# owl-analog.net
KiCad netlist of a schematic drawn in EAGLE
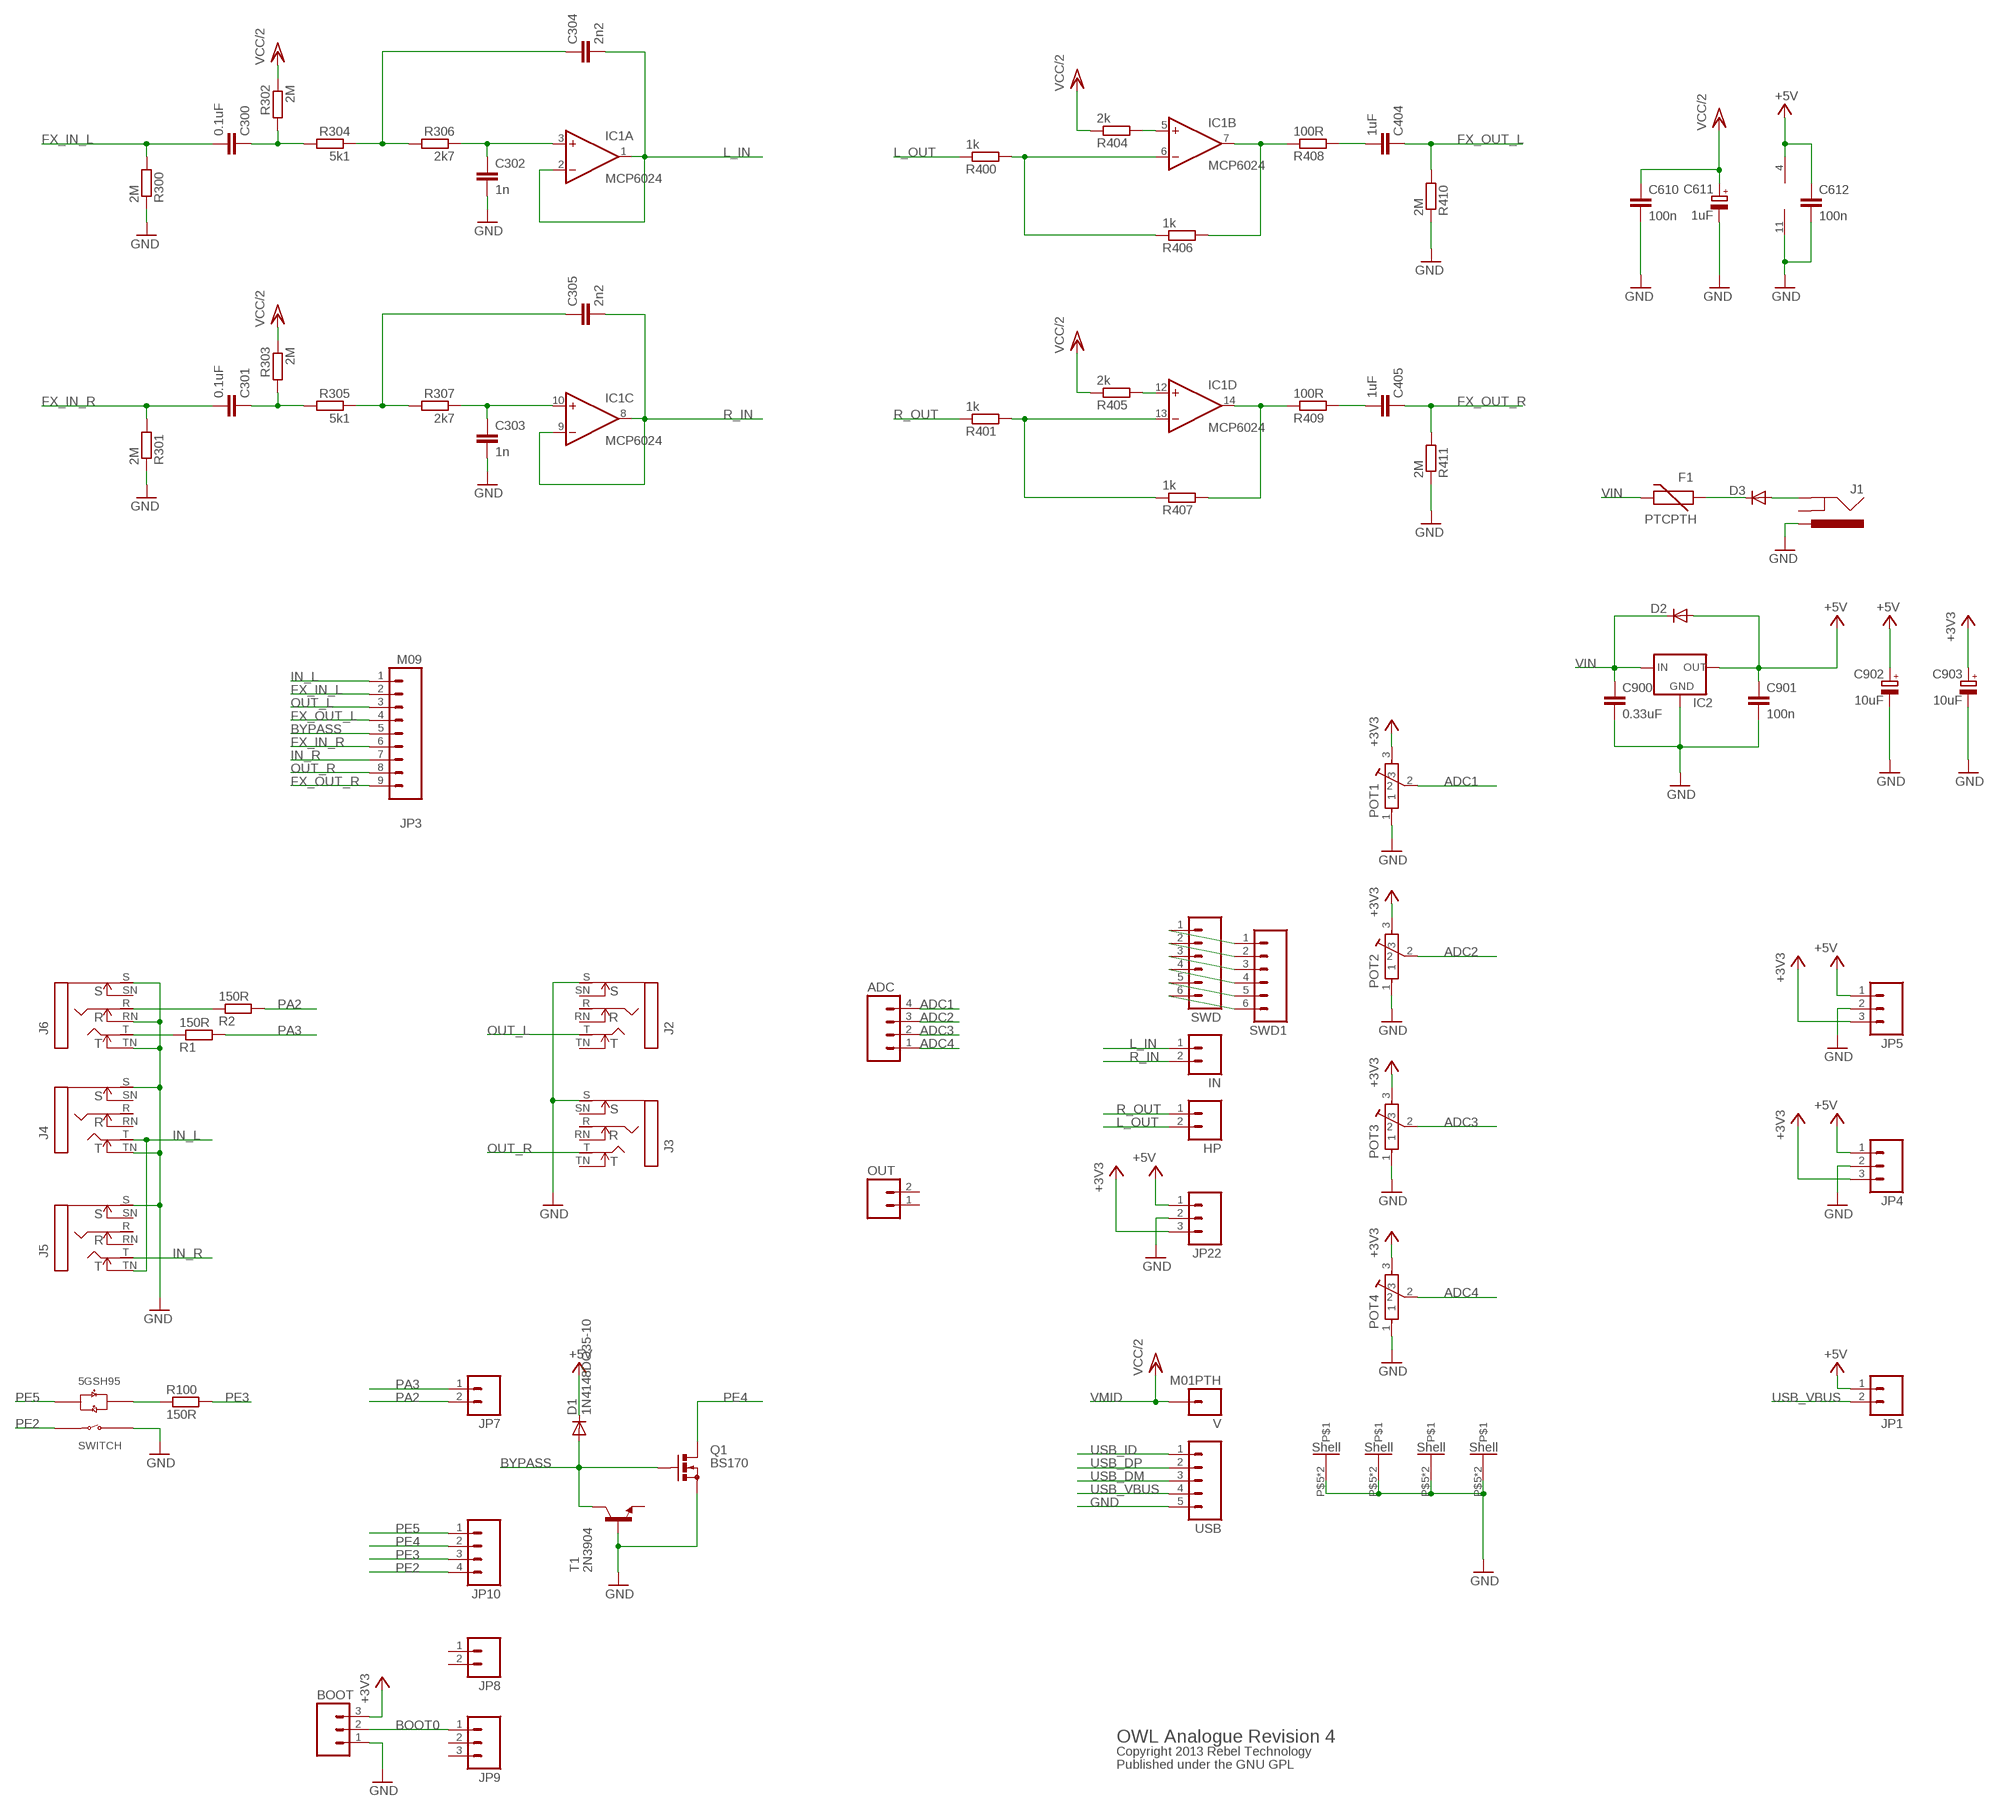
[diagram p0: schematic, sheet 1]

(export (version "E")
  (design (tool "Eeschema 10.0.6"))
  (components
    (comp (ref "ADC")
      (value "M04PTH")
      (footprint "eagle-import:1X04")
      (libsource (lib "eagle-import") (part "M04PTH"))
    )
    (comp (ref "BOOT")
      (value "M03PTH")
      (footprint "eagle-import:1X03")
      (libsource (lib "eagle-import") (part "M03PTH"))
    )
    (comp (ref "C300")
      (value "0.1uF")
      (footprint "eagle-import:C5B3.5")
      (libsource (lib "eagle-import") (part "C5/3.5"))
    )
    (comp (ref "C301")
      (value "0.1uF")
      (footprint "eagle-import:C5B3.5")
      (libsource (lib "eagle-import") (part "C5/3.5"))
    )
    (comp (ref "C302")
      (value "1n")
      (footprint "eagle-import:C5B2.5")
      (libsource (lib "eagle-import") (part "C5/2.5"))
    )
    (comp (ref "C303")
      (value "1n")
      (footprint "eagle-import:C5B2.5")
      (libsource (lib "eagle-import") (part "C5/2.5"))
    )
    (comp (ref "C304")
      (value "2n2")
      (footprint "eagle-import:C5B2.5")
      (libsource (lib "eagle-import") (part "C5/2.5"))
    )
    (comp (ref "C305")
      (value "2n2")
      (footprint "eagle-import:C050-025X075")
      (libsource (lib "eagle-import") (part "C-EU050-025X075"))
    )
    (comp (ref "C404")
      (value "1uF")
      (footprint "eagle-import:C5B5")
      (libsource (lib "eagle-import") (part "C5/5"))
    )
    (comp (ref "C405")
      (value "1uF")
      (footprint "eagle-import:C5B5")
      (libsource (lib "eagle-import") (part "C5/5"))
    )
    (comp (ref "C610")
      (value "100n")
      (footprint "eagle-import:C050-025X075")
      (libsource (lib "eagle-import") (part "C-EU050-025X075"))
    )
    (comp (ref "C611")
      (value "1uF")
      (footprint "eagle-import:E2,5-7")
      (libsource (lib "eagle-import") (part "CPOL-EUE2.5-7"))
    )
    (comp (ref "C612")
      (value "100n")
      (footprint "eagle-import:C050-025X075")
      (libsource (lib "eagle-import") (part "C-EU050-025X075"))
    )
    (comp (ref "C900")
      (value "0.33uF")
      (footprint "eagle-import:C050-025X075")
      (libsource (lib "eagle-import") (part "C-EU050-025X075"))
    )
    (comp (ref "C901")
      (value "100n")
      (footprint "eagle-import:C050-025X075")
      (libsource (lib "eagle-import") (part "C-EU050-025X075"))
    )
    (comp (ref "C902")
      (value "10uF")
      (footprint "eagle-import:E2,5-7")
      (libsource (lib "eagle-import") (part "CPOL-EUE2.5-7"))
    )
    (comp (ref "C903")
      (value "10uF")
      (footprint "eagle-import:E2,5-7")
      (libsource (lib "eagle-import") (part "CPOL-EUE2.5-7"))
    )
    (comp (ref "D1")
      (value "1N4148DO35-10")
      (footprint "eagle-import:DO35-10")
      (libsource (lib "eagle-import") (part "1N4148DO35-10"))
    )
    (comp (ref "D2")
      (value "DIODE1N4001")
      (footprint "eagle-import:DIODE-1N4001")
      (libsource (lib "eagle-import") (part "DIODE1N4001"))
    )
    (comp (ref "D3")
      (value "DIODE1N4001")
      (footprint "eagle-import:DIODE-1N4001")
      (libsource (lib "eagle-import") (part "DIODE1N4001"))
    )
    (comp (ref "F1")
      (value "PTCPTH")
      (footprint "eagle-import:PTC")
      (libsource (lib "eagle-import") (part "PTCPTH"))
    )
    (comp (ref "HP")
      (value "M02PTH")
      (footprint "eagle-import:1X02")
      (libsource (lib "eagle-import") (part "M02PTH"))
    )
    (comp (ref "IC1")
      (value "MCP6024")
      (footprint "eagle-import:DIL14")
      (libsource (lib "eagle-import") (part "TL074P"))
    )
    (comp (ref "IC2")
      (value "V_REG_78XX-TO-220")
      (footprint "eagle-import:TO-220-ALT")
      (libsource (lib "eagle-import") (part "V_REG_78XX-TO-220"))
    )
    (comp (ref "IN")
      (value "M02PTH")
      (footprint "eagle-import:1X02")
      (libsource (lib "eagle-import") (part "M02PTH"))
    )
    (comp (ref "J1")
      (value "POWER_JACKPTH")
      (footprint "eagle-import:POWER_JACK_PTH")
      (libsource (lib "eagle-import") (part "POWER_JACKPTH"))
    )
    (comp (ref "J2")
      (value "NEUTRIK_NMJ6HCD2")
      (footprint "eagle-import:NMJ6HCD2")
      (libsource (lib "eagle-import") (part "NEUTRIK_NMJ6HCD2"))
    )
    (comp (ref "J3")
      (value "NEUTRIK_NMJ6HCD2")
      (footprint "eagle-import:NMJ6HCD2")
      (libsource (lib "eagle-import") (part "NEUTRIK_NMJ6HCD2"))
    )
    (comp (ref "J4")
      (value "NEUTRIK_NMJ6HCD2")
      (footprint "eagle-import:NMJ6HCD2")
      (libsource (lib "eagle-import") (part "NEUTRIK_NMJ6HCD2"))
    )
    (comp (ref "J5")
      (value "NEUTRIK_NMJ6HCD2")
      (footprint "eagle-import:NMJ6HCD2")
      (libsource (lib "eagle-import") (part "NEUTRIK_NMJ6HCD2"))
    )
    (comp (ref "J6")
      (value "NEUTRIK_NMJ6HCD2")
      (footprint "eagle-import:NMJ6HCD2")
      (libsource (lib "eagle-import") (part "NEUTRIK_NMJ6HCD2"))
    )
    (comp (ref "JP1")
      (value "M02PTH")
      (footprint "eagle-import:1X02")
      (libsource (lib "eagle-import") (part "M02PTH"))
    )
    (comp (ref "JP3")
      (value "M09")
      (footprint "eagle-import:1X09")
      (libsource (lib "eagle-import") (part "M09"))
    )
    (comp (ref "JP4")
      (value "M03PTH")
      (footprint "eagle-import:1X03")
      (libsource (lib "eagle-import") (part "M03PTH"))
    )
    (comp (ref "JP5")
      (value "M03PTH")
      (footprint "eagle-import:1X03")
      (libsource (lib "eagle-import") (part "M03PTH"))
    )
    (comp (ref "JP7")
      (value "M02PTH")
      (footprint "eagle-import:1X02")
      (libsource (lib "eagle-import") (part "M02PTH"))
    )
    (comp (ref "JP8")
      (value "M02PTH")
      (footprint "eagle-import:1X02")
      (libsource (lib "eagle-import") (part "M02PTH"))
    )
    (comp (ref "JP9")
      (value "M03PTH")
      (footprint "eagle-import:1X03")
      (libsource (lib "eagle-import") (part "M03PTH"))
    )
    (comp (ref "JP10")
      (value "M04PTH")
      (footprint "eagle-import:1X04")
      (libsource (lib "eagle-import") (part "M04PTH"))
    )
    (comp (ref "JP22")
      (value "M03PTH")
      (footprint "eagle-import:1X03")
      (libsource (lib "eagle-import") (part "M03PTH"))
    )
    (comp (ref "OUT")
      (value "M02PTH")
      (footprint "eagle-import:1X02")
      (libsource (lib "eagle-import") (part "M02PTH"))
    )
    (comp (ref "POT1")
      (value "POT-ALPS-RK09L1140")
      (footprint "eagle-import:POT-ALPS-RK09L1140")
      (libsource (lib "eagle-import") (part "POT-ALPS-RK09L1140"))
    )
    (comp (ref "POT2")
      (value "POT-ALPS-RK09L1140")
      (footprint "eagle-import:POT-ALPS-RK09L1140")
      (libsource (lib "eagle-import") (part "POT-ALPS-RK09L1140"))
    )
    (comp (ref "POT3")
      (value "POT-ALPS-RK09L1140")
      (footprint "eagle-import:POT-ALPS-RK09L1140")
      (libsource (lib "eagle-import") (part "POT-ALPS-RK09L1140"))
    )
    (comp (ref "POT4")
      (value "POT-ALPS-RK09L1140")
      (footprint "eagle-import:POT-ALPS-RK09L1140")
      (libsource (lib "eagle-import") (part "POT-ALPS-RK09L1140"))
    )
    (comp (ref "Q1")
      (value "BS170")
      (footprint "eagle-import:SOT54E")
      (libsource (lib "eagle-import") (part "BS170"))
    )
    (comp (ref "R1")
      (value "150R")
      (footprint "eagle-import:0204_7")
      (libsource (lib "eagle-import") (part "R-EU_0204/7"))
    )
    (comp (ref "R2")
      (value "150R")
      (footprint "eagle-import:0204_7")
      (libsource (lib "eagle-import") (part "R-EU_0204/7"))
    )
    (comp (ref "R100")
      (value "150R")
      (footprint "eagle-import:0204_7")
      (libsource (lib "eagle-import") (part "R-EU_0204/7"))
    )
    (comp (ref "R300")
      (value "2M")
      (footprint "eagle-import:0204_7")
      (libsource (lib "eagle-import") (part "R-EU_0204/7"))
    )
    (comp (ref "R301")
      (value "2M")
      (footprint "eagle-import:0204_7")
      (libsource (lib "eagle-import") (part "R-EU_0204/7"))
    )
    (comp (ref "R302")
      (value "2M")
      (footprint "eagle-import:0204_7")
      (libsource (lib "eagle-import") (part "R-EU_0204/7"))
    )
    (comp (ref "R303")
      (value "2M")
      (footprint "eagle-import:0204_7")
      (libsource (lib "eagle-import") (part "R-EU_0204/7"))
    )
    (comp (ref "R304")
      (value "5k1")
      (footprint "eagle-import:0204_7")
      (libsource (lib "eagle-import") (part "R-EU_0204/7"))
    )
    (comp (ref "R305")
      (value "5k1")
      (footprint "eagle-import:0204_7")
      (libsource (lib "eagle-import") (part "R-EU_0204/7"))
    )
    (comp (ref "R306")
      (value "2k7")
      (footprint "eagle-import:0204_7")
      (libsource (lib "eagle-import") (part "R-EU_0204/7"))
    )
    (comp (ref "R307")
      (value "2k7")
      (footprint "eagle-import:0204_7")
      (libsource (lib "eagle-import") (part "R-EU_0204/7"))
    )
    (comp (ref "R400")
      (value "1k")
      (footprint "eagle-import:0204_7")
      (libsource (lib "eagle-import") (part "R-EU_0204/7"))
    )
    (comp (ref "R401")
      (value "1k")
      (footprint "eagle-import:0204_7")
      (libsource (lib "eagle-import") (part "R-EU_0204/7"))
    )
    (comp (ref "R404")
      (value "2k")
      (footprint "eagle-import:0204_7")
      (libsource (lib "eagle-import") (part "R-EU_0204/7"))
    )
    (comp (ref "R405")
      (value "2k")
      (footprint "eagle-import:0204_7")
      (libsource (lib "eagle-import") (part "R-EU_0204/7"))
    )
    (comp (ref "R406")
      (value "1k")
      (footprint "eagle-import:0204_7")
      (libsource (lib "eagle-import") (part "R-EU_0204/7"))
    )
    (comp (ref "R407")
      (value "1k")
      (footprint "eagle-import:0204_7")
      (libsource (lib "eagle-import") (part "R-EU_0204/7"))
    )
    (comp (ref "R408")
      (value "100R")
      (footprint "eagle-import:0204_7")
      (libsource (lib "eagle-import") (part "R-EU_0204/7"))
    )
    (comp (ref "R409")
      (value "100R")
      (footprint "eagle-import:0204_7")
      (libsource (lib "eagle-import") (part "R-EU_0204/7"))
    )
    (comp (ref "R410")
      (value "2M")
      (footprint "eagle-import:0204_7")
      (libsource (lib "eagle-import") (part "R-EU_0204/7"))
    )
    (comp (ref "R411")
      (value "2M")
      (footprint "eagle-import:0204_7")
      (libsource (lib "eagle-import") (part "R-EU_0204/7"))
    )
    (comp (ref "SWD")
      (value "M06SIP")
      (footprint "eagle-import:1X06")
      (libsource (lib "eagle-import") (part "M06SIP"))
    )
    (comp (ref "SWD1")
      (value "M06SIP")
      (footprint "eagle-import:1X06")
      (libsource (lib "eagle-import") (part "M06SIP"))
    )
    (comp (ref "T1")
      (value "2N3904")
      (footprint "eagle-import:TO92")
      (libsource (lib "eagle-import") (part "2N3904"))
    )
    (comp (ref "U$1")
      (value "5GTH9")
      (footprint "eagle-import:5GTH9")
      (libsource (lib "eagle-import") (part "5GTH9"))
    )
    (comp (ref "USB")
      (value "M05PTH")
      (footprint "eagle-import:1X05")
      (libsource (lib "eagle-import") (part "M05PTH"))
    )
    (comp (ref "V")
      (value "M01PTH")
      (footprint "eagle-import:1X01")
      (libsource (lib "eagle-import") (part "M01PTH"))
    )
  )
  (nets
    (net (code "1") (name "+3V3") (class "Default")
      (node (ref "BOOT") (pin "3") (pinfunction "3_3") (pintype "passive"))
      (node (ref "C903") (pin "+") (pinfunction "+_+") (pintype "passive"))
      (node (ref "JP22") (pin "3") (pinfunction "3_3") (pintype "passive"))
      (node (ref "JP4") (pin "3") (pinfunction "3_3") (pintype "passive"))
      (node (ref "JP5") (pin "3") (pinfunction "3_3") (pintype "passive"))
      (node (ref "POT1") (pin "3") (pinfunction "3_3") (pintype "bidirectional"))
      (node (ref "POT2") (pin "3") (pinfunction "3_3") (pintype "bidirectional"))
      (node (ref "POT3") (pin "3") (pinfunction "3_3") (pintype "bidirectional"))
      (node (ref "POT4") (pin "3") (pinfunction "3_3") (pintype "bidirectional"))
    )
    (net (code "2") (name "+5V") (class "Default")
      (node (ref "C612") (pin "1") (pinfunction "1_1") (pintype "passive"))
      (node (ref "C901") (pin "1") (pinfunction "1_1") (pintype "passive"))
      (node (ref "C902") (pin "+") (pinfunction "+_+") (pintype "passive"))
      (node (ref "D1") (pin "C") (pinfunction "C_C") (pintype "passive"))
      (node (ref "D2") (pin "A") (pinfunction "A_A") (pintype "passive"))
      (node (ref "IC1") (pin "4") (pinfunction "V+_4") (pintype "power_in"))
      (node (ref "IC2") (pin "OUT") (pinfunction "OUT_OUT") (pintype "output"))
      (node (ref "JP1") (pin "1") (pinfunction "1_1") (pintype "passive"))
      (node (ref "JP22") (pin "1") (pinfunction "1_1") (pintype "passive"))
      (node (ref "JP4") (pin "1") (pinfunction "1_1") (pintype "passive"))
      (node (ref "JP5") (pin "1") (pinfunction "1_1") (pintype "passive"))
    )
    (net (code "3") (name "/ADC1") (class "Default")
      (node (ref "ADC") (pin "4") (pinfunction "4_4") (pintype "passive"))
      (node (ref "POT1") (pin "2") (pinfunction "2_2") (pintype "bidirectional"))
    )
    (net (code "4") (name "/ADC2") (class "Default")
      (node (ref "ADC") (pin "3") (pinfunction "3_3") (pintype "passive"))
      (node (ref "POT2") (pin "2") (pinfunction "2_2") (pintype "bidirectional"))
    )
    (net (code "5") (name "/ADC3") (class "Default")
      (node (ref "ADC") (pin "2") (pinfunction "2_2") (pintype "passive"))
      (node (ref "POT3") (pin "2") (pinfunction "2_2") (pintype "bidirectional"))
    )
    (net (code "6") (name "/ADC4") (class "Default")
      (node (ref "ADC") (pin "1") (pinfunction "1_1") (pintype "passive"))
      (node (ref "POT4") (pin "2") (pinfunction "2_2") (pintype "bidirectional"))
    )
    (net (code "7") (name "/BOOT0") (class "Default")
      (node (ref "BOOT") (pin "2") (pinfunction "2_2") (pintype "passive"))
      (node (ref "JP9") (pin "1") (pinfunction "1_1") (pintype "passive"))
    )
    (net (code "8") (name "/BYPASS") (class "Default")
      (node (ref "D1") (pin "A") (pinfunction "A_A") (pintype "passive"))
      (node (ref "JP3") (pin "5") (pinfunction "5_5") (pintype "passive"))
      (node (ref "Q1") (pin "G") (pinfunction "G_G") (pintype "passive"))
      (node (ref "T1") (pin "1") (pinfunction "C_1") (pintype "passive"))
    )
    (net (code "9") (name "/FX_IN_L") (class "Default")
      (node (ref "C300") (pin "2") (pinfunction "2_2") (pintype "passive"))
      (node (ref "JP3") (pin "2") (pinfunction "2_2") (pintype "passive"))
      (node (ref "R300") (pin "2") (pinfunction "2_2") (pintype "passive"))
    )
    (net (code "10") (name "/FX_IN_R") (class "Default")
      (node (ref "C301") (pin "2") (pinfunction "2_2") (pintype "passive"))
      (node (ref "JP3") (pin "6") (pinfunction "6_6") (pintype "passive"))
      (node (ref "R301") (pin "2") (pinfunction "2_2") (pintype "passive"))
    )
    (net (code "11") (name "/FX_OUT_L") (class "Default")
      (node (ref "C404") (pin "1") (pinfunction "1_1") (pintype "passive"))
      (node (ref "JP3") (pin "4") (pinfunction "4_4") (pintype "passive"))
      (node (ref "R410") (pin "2") (pinfunction "2_2") (pintype "passive"))
    )
    (net (code "12") (name "/FX_OUT_R") (class "Default")
      (node (ref "C405") (pin "1") (pinfunction "1_1") (pintype "passive"))
      (node (ref "JP3") (pin "9") (pinfunction "9_9") (pintype "passive"))
      (node (ref "R411") (pin "2") (pinfunction "2_2") (pintype "passive"))
    )
    (net (code "13") (name "/IN_L") (class "Default")
      (node (ref "J4") (pin "T") (pinfunction "T_T") (pintype "passive"))
      (node (ref "J5") (pin "TN") (pinfunction "TN_TN") (pintype "passive"))
      (node (ref "JP3") (pin "1") (pinfunction "1_1") (pintype "passive"))
    )
    (net (code "14") (name "/IN_R") (class "Default")
      (node (ref "J5") (pin "T") (pinfunction "T_T") (pintype "passive"))
      (node (ref "JP3") (pin "7") (pinfunction "7_7") (pintype "passive"))
    )
    (net (code "15") (name "/L_IN") (class "Default")
      (node (ref "C304") (pin "2") (pinfunction "2_2") (pintype "passive"))
      (node (ref "IC1") (pin "1") (pinfunction "OUT_1") (pintype "output"))
      (node (ref "IC1") (pin "2") (pinfunction "-IN_2") (pintype "input"))
      (node (ref "IN") (pin "1") (pinfunction "1_1") (pintype "passive"))
    )
    (net (code "16") (name "/L_OUT") (class "Default")
      (node (ref "HP") (pin "2") (pinfunction "2_2") (pintype "passive"))
      (node (ref "R400") (pin "1") (pinfunction "1_1") (pintype "passive"))
    )
    (net (code "17") (name "/OUT_L") (class "Default")
      (node (ref "J2") (pin "T") (pinfunction "T_T") (pintype "passive"))
      (node (ref "JP3") (pin "3") (pinfunction "3_3") (pintype "passive"))
    )
    (net (code "18") (name "/OUT_R") (class "Default")
      (node (ref "J3") (pin "T") (pinfunction "T_T") (pintype "passive"))
      (node (ref "JP3") (pin "8") (pinfunction "8_8") (pintype "passive"))
    )
    (net (code "19") (name "/PA2") (class "Default")
      (node (ref "JP7") (pin "2") (pinfunction "2_2") (pintype "passive"))
      (node (ref "R2") (pin "2") (pinfunction "2_2") (pintype "passive"))
    )
    (net (code "20") (name "/PA3") (class "Default")
      (node (ref "JP7") (pin "1") (pinfunction "1_1") (pintype "passive"))
      (node (ref "R1") (pin "2") (pinfunction "2_2") (pintype "passive"))
    )
    (net (code "21") (name "/PE2") (class "Default")
      (node (ref "JP10") (pin "4") (pinfunction "4_4") (pintype "passive"))
      (node (ref "U$1") (pin "4") (pinfunction "SWITCH_A_4") (pintype "power_in"))
    )
    (net (code "22") (name "/PE3") (class "Default")
      (node (ref "JP10") (pin "3") (pinfunction "3_3") (pintype "passive"))
      (node (ref "R100") (pin "2") (pinfunction "2_2") (pintype "passive"))
    )
    (net (code "23") (name "/PE4") (class "Default")
      (node (ref "JP10") (pin "2") (pinfunction "2_2") (pintype "passive"))
      (node (ref "Q1") (pin "D") (pinfunction "D_D") (pintype "passive"))
    )
    (net (code "24") (name "/PE5") (class "Default")
      (node (ref "JP10") (pin "1") (pinfunction "1_1") (pintype "passive"))
      (node (ref "U$1") (pin "-2") (pinfunction "LED_G+_-2") (pintype "input"))
    )
    (net (code "25") (name "/R_IN") (class "Default")
      (node (ref "C305") (pin "2") (pinfunction "2_2") (pintype "passive"))
      (node (ref "IC1") (pin "8") (pinfunction "OUT_8") (pintype "output"))
      (node (ref "IC1") (pin "9") (pinfunction "-IN_9") (pintype "input"))
      (node (ref "IN") (pin "2") (pinfunction "2_2") (pintype "passive"))
    )
    (net (code "26") (name "/R_OUT") (class "Default")
      (node (ref "HP") (pin "1") (pinfunction "1_1") (pintype "passive"))
      (node (ref "R401") (pin "1") (pinfunction "1_1") (pintype "passive"))
    )
    (net (code "27") (name "/USB_DM") (class "Default")
      (node (ref "USB") (pin "3") (pinfunction "3_3") (pintype "passive"))
    )
    (net (code "28") (name "/USB_DP") (class "Default")
      (node (ref "USB") (pin "2") (pinfunction "2_2") (pintype "passive"))
    )
    (net (code "29") (name "/USB_ID") (class "Default")
      (node (ref "USB") (pin "1") (pinfunction "1_1") (pintype "passive"))
    )
    (net (code "30") (name "/USB_VBUS") (class "Default")
      (node (ref "JP1") (pin "2") (pinfunction "2_2") (pintype "passive"))
      (node (ref "USB") (pin "4") (pinfunction "4_4") (pintype "passive"))
    )
    (net (code "31") (name "/VIN") (class "Default")
      (node (ref "C900") (pin "1") (pinfunction "1_1") (pintype "passive"))
      (node (ref "D2") (pin "C") (pinfunction "C_C") (pintype "passive"))
      (node (ref "F1") (pin "P$2") (pinfunction "2_P$2") (pintype "bidirectional"))
      (node (ref "IC2") (pin "IN") (pinfunction "IN_IN") (pintype "input"))
    )
    (net (code "32") (name "GND") (class "Default")
      (node (ref "BOOT") (pin "1") (pinfunction "1_1") (pintype "passive"))
      (node (ref "C302") (pin "2") (pinfunction "2_2") (pintype "passive"))
      (node (ref "C303") (pin "2") (pinfunction "2_2") (pintype "passive"))
      (node (ref "C610") (pin "2") (pinfunction "2_2") (pintype "passive"))
      (node (ref "C611") (pin "-") (pinfunction "-_-") (pintype "passive"))
      (node (ref "C612") (pin "2") (pinfunction "2_2") (pintype "passive"))
      (node (ref "C900") (pin "2") (pinfunction "2_2") (pintype "passive"))
      (node (ref "C901") (pin "2") (pinfunction "2_2") (pintype "passive"))
      (node (ref "C902") (pin "-") (pinfunction "-_-") (pintype "passive"))
      (node (ref "C903") (pin "-") (pinfunction "-_-") (pintype "passive"))
      (node (ref "IC1") (pin "11") (pinfunction "V-_11") (pintype "power_in"))
      (node (ref "IC2") (pin "GND") (pinfunction "GND_GND") (pintype "input"))
      (node (ref "J1") (pin "PWR") (pinfunction "PWR_PWR") (pintype "bidirectional"))
      (node (ref "J2") (pin "S") (pinfunction "S_S") (pintype "passive"))
      (node (ref "J3") (pin "S") (pinfunction "S_S") (pintype "passive"))
      (node (ref "J4") (pin "S") (pinfunction "S_S") (pintype "passive"))
      (node (ref "J4") (pin "TN") (pinfunction "TN_TN") (pintype "passive"))
      (node (ref "J5") (pin "S") (pinfunction "S_S") (pintype "passive"))
      (node (ref "J6") (pin "RN") (pinfunction "RN_RN") (pintype "passive"))
      (node (ref "J6") (pin "S") (pinfunction "S_S") (pintype "passive"))
      (node (ref "J6") (pin "TN") (pinfunction "TN_TN") (pintype "passive"))
      (node (ref "JP22") (pin "2") (pinfunction "2_2") (pintype "passive"))
      (node (ref "JP4") (pin "2") (pinfunction "2_2") (pintype "passive"))
      (node (ref "JP5") (pin "2") (pinfunction "2_2") (pintype "passive"))
      (node (ref "POT1") (pin "1") (pinfunction "1_1") (pintype "bidirectional"))
      (node (ref "POT1") (pin "P$5") (pinfunction "P$1_P$5") (pintype "bidirectional"))
      (node (ref "POT1") (pin "P$6") (pinfunction "P$1_P$6") (pintype "bidirectional"))
      (node (ref "POT2") (pin "1") (pinfunction "1_1") (pintype "bidirectional"))
      (node (ref "POT2") (pin "P$5") (pinfunction "P$1_P$5") (pintype "bidirectional"))
      (node (ref "POT2") (pin "P$6") (pinfunction "P$1_P$6") (pintype "bidirectional"))
      (node (ref "POT3") (pin "1") (pinfunction "1_1") (pintype "bidirectional"))
      (node (ref "POT3") (pin "P$5") (pinfunction "P$1_P$5") (pintype "bidirectional"))
      (node (ref "POT3") (pin "P$6") (pinfunction "P$1_P$6") (pintype "bidirectional"))
      (node (ref "POT4") (pin "1") (pinfunction "1_1") (pintype "bidirectional"))
      (node (ref "POT4") (pin "P$5") (pinfunction "P$1_P$5") (pintype "bidirectional"))
      (node (ref "POT4") (pin "P$6") (pinfunction "P$1_P$6") (pintype "bidirectional"))
      (node (ref "Q1") (pin "S") (pinfunction "S_S") (pintype "passive"))
      (node (ref "R300") (pin "1") (pinfunction "1_1") (pintype "passive"))
      (node (ref "R301") (pin "1") (pinfunction "1_1") (pintype "passive"))
      (node (ref "R410") (pin "1") (pinfunction "1_1") (pintype "passive"))
      (node (ref "R411") (pin "1") (pinfunction "1_1") (pintype "passive"))
      (node (ref "T1") (pin "2") (pinfunction "B_2") (pintype "passive"))
      (node (ref "U$1") (pin "1") (pinfunction "SWITCH_B_1") (pintype "power_in"))
      (node (ref "USB") (pin "5") (pinfunction "5_5") (pintype "passive"))
    )
    (net (code "33") (name "Net-(C300-Pad1)") (class "Default")
      (node (ref "C300") (pin "1") (pinfunction "1_1") (pintype "passive"))
      (node (ref "R302") (pin "2") (pinfunction "2_2") (pintype "passive"))
      (node (ref "R304") (pin "2") (pinfunction "2_2") (pintype "passive"))
    )
    (net (code "34") (name "Net-(C301-Pad1)") (class "Default")
      (node (ref "C301") (pin "1") (pinfunction "1_1") (pintype "passive"))
      (node (ref "R303") (pin "2") (pinfunction "2_2") (pintype "passive"))
      (node (ref "R305") (pin "2") (pinfunction "2_2") (pintype "passive"))
    )
    (net (code "35") (name "Net-(C304-Pad1)") (class "Default")
      (node (ref "C304") (pin "1") (pinfunction "1_1") (pintype "passive"))
      (node (ref "R304") (pin "1") (pinfunction "1_1") (pintype "passive"))
      (node (ref "R306") (pin "2") (pinfunction "2_2") (pintype "passive"))
    )
    (net (code "36") (name "Net-(C305-Pad1)") (class "Default")
      (node (ref "C305") (pin "1") (pinfunction "1_1") (pintype "passive"))
      (node (ref "R305") (pin "1") (pinfunction "1_1") (pintype "passive"))
      (node (ref "R307") (pin "2") (pinfunction "2_2") (pintype "passive"))
    )
    (net (code "37") (name "Net-(C404-Pad2)") (class "Default")
      (node (ref "C404") (pin "2") (pinfunction "2_2") (pintype "passive"))
      (node (ref "R408") (pin "2") (pinfunction "2_2") (pintype "passive"))
    )
    (net (code "38") (name "Net-(C405-Pad2)") (class "Default")
      (node (ref "C405") (pin "2") (pinfunction "2_2") (pintype "passive"))
      (node (ref "R409") (pin "2") (pinfunction "2_2") (pintype "passive"))
    )
    (net (code "39") (name "Net-(D3-PadA)") (class "Default")
      (node (ref "D3") (pin "A") (pinfunction "A_A") (pintype "passive"))
      (node (ref "J1") (pin "GND") (pinfunction "GND_GND") (pintype "bidirectional"))
    )
    (net (code "40") (name "Net-(F1-1)") (class "Default")
      (node (ref "D3") (pin "C") (pinfunction "C_C") (pintype "passive"))
      (node (ref "F1") (pin "P$1") (pinfunction "1_P$1") (pintype "bidirectional"))
    )
    (net (code "41") (name "Net-(IC1A-+IN)") (class "Default")
      (node (ref "C302") (pin "1") (pinfunction "1_1") (pintype "passive"))
      (node (ref "IC1") (pin "3") (pinfunction "+IN_3") (pintype "input"))
      (node (ref "R306") (pin "1") (pinfunction "1_1") (pintype "passive"))
    )
    (net (code "42") (name "Net-(IC1B-+IN)") (class "Default")
      (node (ref "IC1") (pin "5") (pinfunction "+IN_5") (pintype "input"))
      (node (ref "R404") (pin "2") (pinfunction "2_2") (pintype "passive"))
    )
    (net (code "43") (name "Net-(IC1B--IN)") (class "Default")
      (node (ref "IC1") (pin "6") (pinfunction "-IN_6") (pintype "input"))
      (node (ref "R400") (pin "2") (pinfunction "2_2") (pintype "passive"))
      (node (ref "R406") (pin "1") (pinfunction "1_1") (pintype "passive"))
    )
    (net (code "44") (name "Net-(IC1B-OUT)") (class "Default")
      (node (ref "IC1") (pin "7") (pinfunction "OUT_7") (pintype "output"))
      (node (ref "R406") (pin "2") (pinfunction "2_2") (pintype "passive"))
      (node (ref "R408") (pin "1") (pinfunction "1_1") (pintype "passive"))
    )
    (net (code "45") (name "Net-(IC1C-+IN)") (class "Default")
      (node (ref "C303") (pin "1") (pinfunction "1_1") (pintype "passive"))
      (node (ref "IC1") (pin "10") (pinfunction "+IN_10") (pintype "input"))
      (node (ref "R307") (pin "1") (pinfunction "1_1") (pintype "passive"))
    )
    (net (code "46") (name "Net-(IC1D-+IN)") (class "Default")
      (node (ref "IC1") (pin "12") (pinfunction "+IN_12") (pintype "input"))
      (node (ref "R405") (pin "2") (pinfunction "2_2") (pintype "passive"))
    )
    (net (code "47") (name "Net-(IC1D--IN)") (class "Default")
      (node (ref "IC1") (pin "13") (pinfunction "-IN_13") (pintype "input"))
      (node (ref "R401") (pin "2") (pinfunction "2_2") (pintype "passive"))
      (node (ref "R407") (pin "1") (pinfunction "1_1") (pintype "passive"))
    )
    (net (code "48") (name "Net-(IC1D-OUT)") (class "Default")
      (node (ref "IC1") (pin "14") (pinfunction "OUT_14") (pintype "output"))
      (node (ref "R407") (pin "2") (pinfunction "2_2") (pintype "passive"))
      (node (ref "R409") (pin "1") (pinfunction "1_1") (pintype "passive"))
    )
    (net (code "49") (name "Net-(J6-PadR)") (class "Default")
      (node (ref "J6") (pin "R") (pinfunction "R_R") (pintype "passive"))
      (node (ref "R2") (pin "1") (pinfunction "1_1") (pintype "passive"))
    )
    (net (code "50") (name "Net-(J6-PadT)") (class "Default")
      (node (ref "J6") (pin "T") (pinfunction "T_T") (pintype "passive"))
      (node (ref "R1") (pin "1") (pinfunction "1_1") (pintype "passive"))
    )
    (net (code "51") (name "Net-(SWD-Pad1)") (class "Default")
      (node (ref "SWD") (pin "1") (pinfunction "1_1") (pintype "passive"))
      (node (ref "SWD1") (pin "1") (pinfunction "1_1") (pintype "passive"))
    )
    (net (code "52") (name "Net-(SWD-Pad2)") (class "Default")
      (node (ref "SWD") (pin "2") (pinfunction "2_2") (pintype "passive"))
      (node (ref "SWD1") (pin "2") (pinfunction "2_2") (pintype "passive"))
    )
    (net (code "53") (name "Net-(SWD-Pad3)") (class "Default")
      (node (ref "SWD") (pin "3") (pinfunction "3_3") (pintype "passive"))
      (node (ref "SWD1") (pin "3") (pinfunction "3_3") (pintype "passive"))
    )
    (net (code "54") (name "Net-(SWD-Pad4)") (class "Default")
      (node (ref "SWD") (pin "4") (pinfunction "4_4") (pintype "passive"))
      (node (ref "SWD1") (pin "4") (pinfunction "4_4") (pintype "passive"))
    )
    (net (code "55") (name "Net-(SWD-Pad5)") (class "Default")
      (node (ref "SWD") (pin "5") (pinfunction "5_5") (pintype "passive"))
      (node (ref "SWD1") (pin "5") (pinfunction "5_5") (pintype "passive"))
    )
    (net (code "56") (name "Net-(SWD-Pad6)") (class "Default")
      (node (ref "SWD") (pin "6") (pinfunction "6_6") (pintype "passive"))
      (node (ref "SWD1") (pin "6") (pinfunction "6_6") (pintype "passive"))
    )
    (net (code "57") (name "Net-(U$1-LED_R+)") (class "Default")
      (node (ref "R100") (pin "1") (pinfunction "1_1") (pintype "passive"))
      (node (ref "U$1") (pin "+3") (pinfunction "LED_R+_+3") (pintype "input"))
    )
    (net (code "58") (name "VCC{slash}2") (class "Default")
      (node (ref "C610") (pin "1") (pinfunction "1_1") (pintype "passive"))
      (node (ref "C611") (pin "+") (pinfunction "+_+") (pintype "passive"))
      (node (ref "R302") (pin "1") (pinfunction "1_1") (pintype "passive"))
      (node (ref "R303") (pin "1") (pinfunction "1_1") (pintype "passive"))
      (node (ref "R404") (pin "1") (pinfunction "1_1") (pintype "passive"))
      (node (ref "R405") (pin "1") (pinfunction "1_1") (pintype "passive"))
      (node (ref "V") (pin "1") (pinfunction "1_1") (pintype "passive"))
    )
    (net (code "59") (name "unconnected-(J1-PadGNDBREAK)") (class "Default")
      (node (ref "J1") (pin "GNDBREAK") (pinfunction "GNDBREAK_GNDBREAK") (pintype "bidirectional"))
    )
    (net (code "60") (name "unconnected-(J2-PadR)") (class "Default")
      (node (ref "J2") (pin "R") (pinfunction "R_R") (pintype "passive"))
    )
    (net (code "61") (name "unconnected-(J2-PadRN)") (class "Default")
      (node (ref "J2") (pin "RN") (pinfunction "RN_RN") (pintype "passive"))
    )
    (net (code "62") (name "unconnected-(J2-PadSN)") (class "Default")
      (node (ref "J2") (pin "SN") (pinfunction "SN_SN") (pintype "passive"))
    )
    (net (code "63") (name "unconnected-(J2-PadTN)") (class "Default")
      (node (ref "J2") (pin "TN") (pinfunction "TN_TN") (pintype "passive"))
    )
    (net (code "64") (name "unconnected-(J3-PadR)") (class "Default")
      (node (ref "J3") (pin "R") (pinfunction "R_R") (pintype "passive"))
    )
    (net (code "65") (name "unconnected-(J3-PadRN)") (class "Default")
      (node (ref "J3") (pin "RN") (pinfunction "RN_RN") (pintype "passive"))
    )
    (net (code "66") (name "unconnected-(J3-PadSN)") (class "Default")
      (node (ref "J3") (pin "SN") (pinfunction "SN_SN") (pintype "passive"))
    )
    (net (code "67") (name "unconnected-(J3-PadTN)") (class "Default")
      (node (ref "J3") (pin "TN") (pinfunction "TN_TN") (pintype "passive"))
    )
    (net (code "68") (name "unconnected-(J4-PadR)") (class "Default")
      (node (ref "J4") (pin "R") (pinfunction "R_R") (pintype "passive"))
    )
    (net (code "69") (name "unconnected-(J4-PadRN)") (class "Default")
      (node (ref "J4") (pin "RN") (pinfunction "RN_RN") (pintype "passive"))
    )
    (net (code "70") (name "unconnected-(J4-PadSN)") (class "Default")
      (node (ref "J4") (pin "SN") (pinfunction "SN_SN") (pintype "passive"))
    )
    (net (code "71") (name "unconnected-(J5-PadR)") (class "Default")
      (node (ref "J5") (pin "R") (pinfunction "R_R") (pintype "passive"))
    )
    (net (code "72") (name "unconnected-(J5-PadRN)") (class "Default")
      (node (ref "J5") (pin "RN") (pinfunction "RN_RN") (pintype "passive"))
    )
    (net (code "73") (name "unconnected-(J5-PadSN)") (class "Default")
      (node (ref "J5") (pin "SN") (pinfunction "SN_SN") (pintype "passive"))
    )
    (net (code "74") (name "unconnected-(J6-PadSN)") (class "Default")
      (node (ref "J6") (pin "SN") (pinfunction "SN_SN") (pintype "passive"))
    )
    (net (code "75") (name "unconnected-(JP8-Pad1)") (class "Default")
      (node (ref "JP8") (pin "1") (pinfunction "1_1") (pintype "passive"))
    )
    (net (code "76") (name "unconnected-(JP8-Pad2)") (class "Default")
      (node (ref "JP8") (pin "2") (pinfunction "2_2") (pintype "passive"))
    )
    (net (code "77") (name "unconnected-(JP9-Pad2)") (class "Default")
      (node (ref "JP9") (pin "2") (pinfunction "2_2") (pintype "passive"))
    )
    (net (code "78") (name "unconnected-(JP9-Pad3)") (class "Default")
      (node (ref "JP9") (pin "3") (pinfunction "3_3") (pintype "passive"))
    )
    (net (code "79") (name "unconnected-(OUT-Pad1)") (class "Default")
      (node (ref "OUT") (pin "1") (pinfunction "1_1") (pintype "passive"))
    )
    (net (code "80") (name "unconnected-(OUT-Pad2)") (class "Default")
      (node (ref "OUT") (pin "2") (pinfunction "2_2") (pintype "passive"))
    )
    (net (code "81") (name "unconnected-(T1-E-Pad3)") (class "Default")
      (node (ref "T1") (pin "3") (pinfunction "E_3") (pintype "passive"))
    )
  )
)
